# Lilypad_Schematic_1.net
KiCad netlist of a schematic drawn in Altium Designer
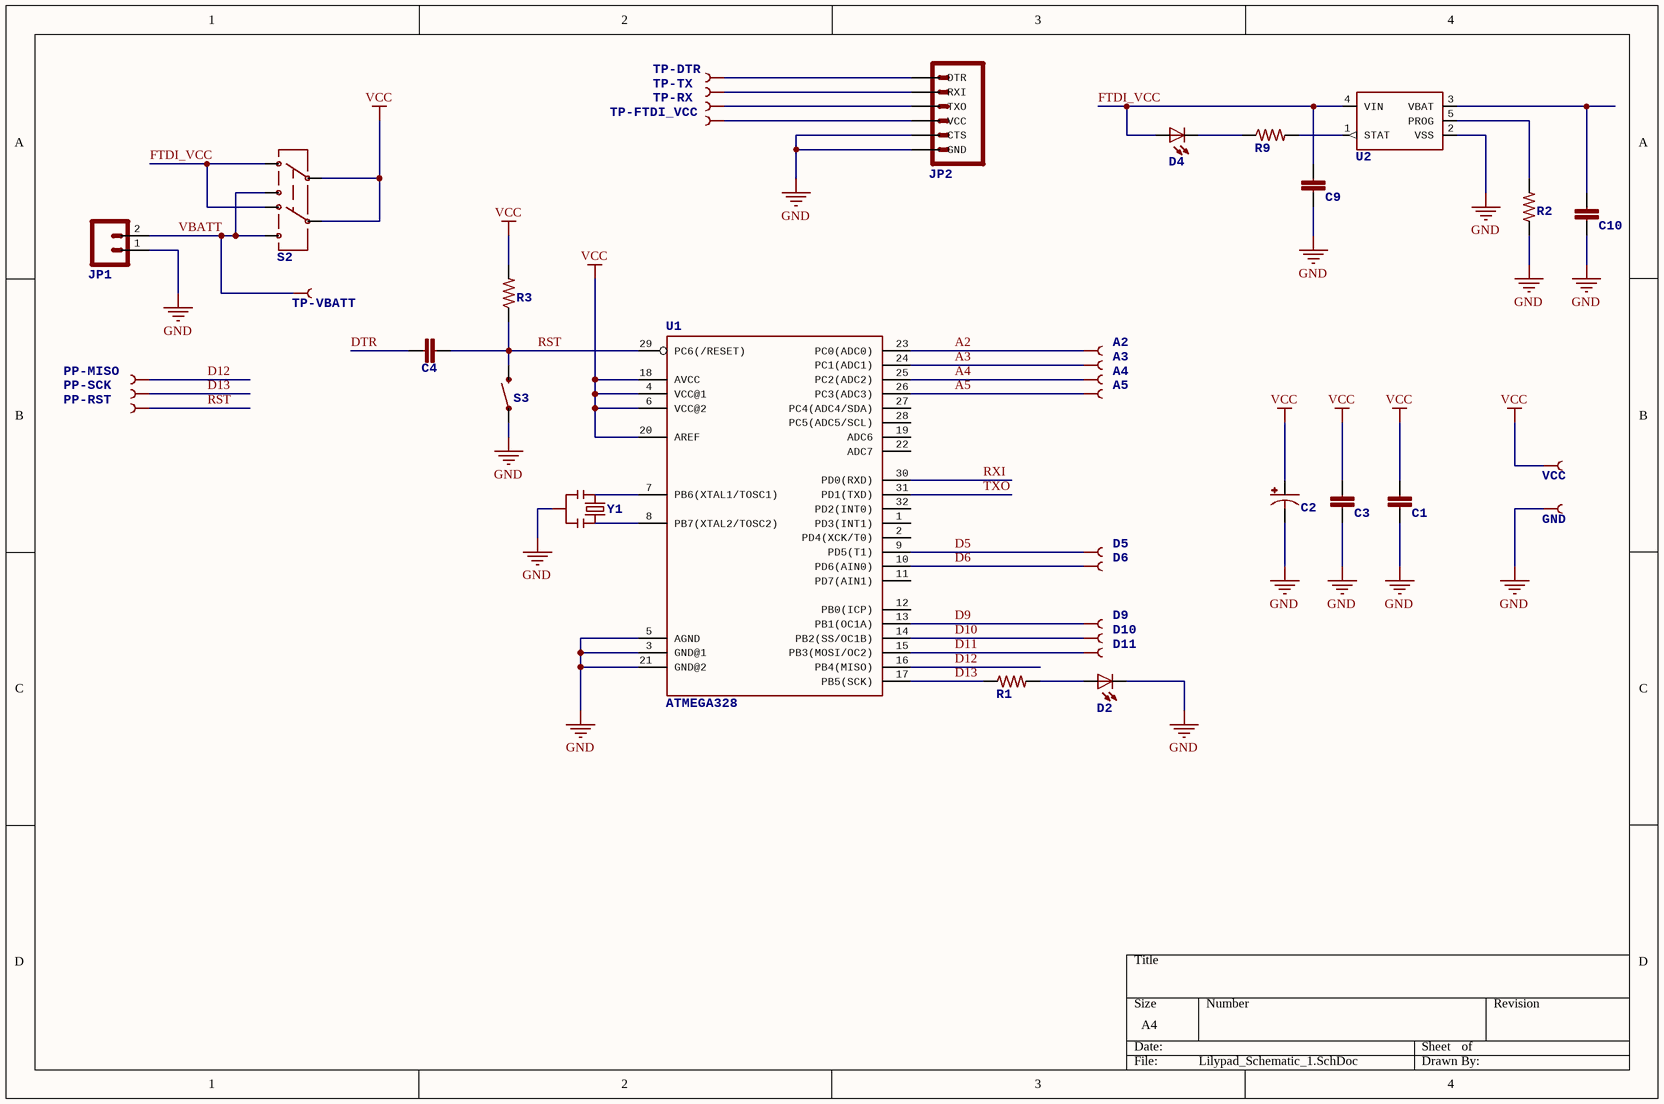
[diagram p0: Lilypad_Schematic_1.SchDoc]

(export (version "E")
  (design (tool "Eeschema 10.0.6"))
  (components
    (comp (ref "A2")
      (value "CONN")
      (footprint "PETAL-LONG-2")
      (libsource (lib "LilyPad Simple v2") (part "CONN"))
    )
    (comp (ref "A3")
      (value "CONN")
      (footprint "PETAL-LONG-2")
      (libsource (lib "LilyPad Simple v2") (part "CONN"))
    )
    (comp (ref "A4")
      (value "CONN")
      (footprint "PETAL-LONG-2")
      (libsource (lib "LilyPad Simple v2") (part "CONN"))
    )
    (comp (ref "A5")
      (value "CONN")
      (footprint "PETAL-LONG-2")
      (libsource (lib "LilyPad Simple v2") (part "CONN"))
    )
    (comp (ref "C1")
      (value "CAP0402-CAP")
      (footprint "0402-CAP")
      (libsource (lib "LilyPad Simple v2") (part "CAP0402-CAP"))
    )
    (comp (ref "C2")
      (value "CAP_POL3528")
      (footprint "EIA3528")
      (libsource (lib "LilyPad Simple v2") (part "CAP_POL3528"))
    )
    (comp (ref "C3")
      (value "CAP0402-CAP")
      (footprint "0402-CAP")
      (libsource (lib "LilyPad Simple v2") (part "CAP0402-CAP"))
    )
    (comp (ref "C4") (value "CAP0402-CAP") (footprint "0402-CAP") (libsource (lib "") (part "CAP0402-CAP_1")))
    (comp (ref "C9")
      (value "CAP0402-CAP")
      (footprint "0402-CAP")
      (libsource (lib "LilyPad Simple v2") (part "CAP0402-CAP"))
    )
    (comp (ref "C10")
      (value "CAP0402-CAP")
      (footprint "0402-CAP")
      (libsource (lib "LilyPad Simple v2") (part "CAP0402-CAP"))
    )
    (comp (ref "D2")
      (value "LED0603")
      (footprint "LED-0603")
      (libsource (lib "LilyPad Simple v2") (part "LED0603"))
    )
    (comp (ref "D4")
      (value "LED0603")
      (footprint "LED-0603")
      (libsource (lib "LilyPad Simple v2") (part "LED0603"))
    )
    (comp (ref "D5")
      (value "CONN")
      (footprint "PETAL-LONG-2")
      (libsource (lib "LilyPad Simple v2") (part "CONN"))
    )
    (comp (ref "D6")
      (value "CONN")
      (footprint "PETAL-LONG-2")
      (libsource (lib "LilyPad Simple v2") (part "CONN"))
    )
    (comp (ref "D9")
      (value "CONN")
      (footprint "PETAL-LONG-2")
      (libsource (lib "LilyPad Simple v2") (part "CONN"))
    )
    (comp (ref "D10")
      (value "CONN")
      (footprint "PETAL-LONG-2")
      (libsource (lib "LilyPad Simple v2") (part "CONN"))
    )
    (comp (ref "D11")
      (value "CONN")
      (footprint "PETAL-LONG-2")
      (libsource (lib "LilyPad Simple v2") (part "CONN"))
    )
    (comp (ref "GND")
      (value "CONN")
      (footprint "PETAL-LONG-2")
      (libsource (lib "LilyPad Simple v2") (part "CONN"))
    )
    (comp (ref "JP1")
      (value "M02-JST-2MM-SMT")
      (footprint "JST-2-SMD")
      (libsource (lib "LilyPad Simple v2") (part "M02-JST-2MM-SMT"))
    )
    (comp (ref "JP2")
      (value "ARDUINO_SERIAL_PROGRAMSMD")
      (footprint "1X06-SMD")
      (libsource (lib "LilyPad Simple v2") (part "ARDUINO_SERIAL_PROGRAMSMD"))
    )
    (comp (ref "PP-MISO")
      (value "TEST-POINT3X5")
      (footprint "PAD.03X.05")
      (libsource (lib "LilyPad Simple v2") (part "TEST-POINT3X5"))
    )
    (comp (ref "PP-RST")
      (value "TEST-POINT3X5")
      (footprint "PAD.03X.05")
      (libsource (lib "LilyPad Simple v2") (part "TEST-POINT3X5"))
    )
    (comp (ref "PP-SCK")
      (value "TEST-POINT3X5")
      (footprint "PAD.03X.05")
      (libsource (lib "LilyPad Simple v2") (part "TEST-POINT3X5"))
    )
    (comp (ref "R1")
      (value "RESISTOR0402-RES")
      (footprint "0402-RES")
      (libsource (lib "LilyPad Simple v2") (part "RESISTOR0402-RES"))
    )
    (comp (ref "R2")
      (value "RESISTOR0402-RES")
      (footprint "0402-RES")
      (libsource (lib "LilyPad Simple v2") (part "RESISTOR0402-RES"))
    )
    (comp (ref "R3")
      (value "RESISTOR0402-RES")
      (footprint "0402-RES")
      (libsource (lib "LilyPad Simple v2") (part "RESISTOR0402-RES"))
    )
    (comp (ref "R9")
      (value "RESISTOR0402-RES")
      (footprint "0402-RES")
      (libsource (lib "LilyPad Simple v2") (part "RESISTOR0402-RES"))
    )
    (comp (ref "S2")
      (value "AYZ0202")
      (footprint "AYZ0202")
      (libsource (lib "LilyPad Simple v2") (part "AYZ0202"))
    )
    (comp (ref "S3")
      (value "SWITCH-MOMENTARY-2SMD-2")
      (footprint "TACTILE_SWITCH_SMD-2")
      (libsource (lib "LilyPad Simple v2") (part "SWITCH-MOMENTARY-2SMD-2"))
    )
    (comp (ref "TP-DTR")
      (value "TEST-POINT3X5")
      (footprint "PAD.03X.05")
      (libsource (lib "LilyPad Simple v2") (part "TEST-POINT3X5"))
    )
    (comp (ref "TP-FTDI_VCC")
      (value "TEST-POINT3X5")
      (footprint "PAD.03X.05")
      (libsource (lib "LilyPad Simple v2") (part "TEST-POINT3X5"))
    )
    (comp (ref "TP-RX")
      (value "TEST-POINT3X5")
      (footprint "PAD.03X.05")
      (libsource (lib "LilyPad Simple v2") (part "TEST-POINT3X5"))
    )
    (comp (ref "TP-TX")
      (value "TEST-POINT3X5")
      (footprint "PAD.03X.05")
      (libsource (lib "LilyPad Simple v2") (part "TEST-POINT3X5"))
    )
    (comp (ref "TP-VBATT")
      (value "TEST-POINT3X5")
      (footprint "PAD.03X.05")
      (libsource (lib "LilyPad Simple v2") (part "TEST-POINT3X5"))
    )
    (comp (ref "U1")
      (value "ATMEGA328")
      (footprint "TQFP32-08")
      (libsource (lib "LilyPad Simple v2") (part "ATMEGA328"))
    )
    (comp (ref "U2")
      (value "MCP73831")
      (footprint "SOT23-5")
      (libsource (lib "LilyPad Simple v2") (part "MCP73831"))
    )
    (comp (ref "VCC")
      (value "CONN")
      (footprint "PETAL-LONG-2")
      (libsource (lib "LilyPad Simple v2") (part "CONN"))
    )
    (comp (ref "Y1")
      (value "RESONATORSMD")
      (footprint "RESONATOR-SMD")
      (libsource (lib "LilyPad Simple v2") (part "RESONATORSMD"))
    )
  )
  (nets
    (net (code "1") (name "/A2") (class "Default")
      (node (ref "A2") (pin "1") (pinfunction "1_1") (pintype "passive"))
      (node (ref "U1") (pin "23") (pinfunction "PC0(ADC0)_23") (pintype "passive"))
    )
    (net (code "2") (name "/A3") (class "Default")
      (node (ref "A3") (pin "1") (pinfunction "1_1") (pintype "passive"))
      (node (ref "U1") (pin "24") (pinfunction "PC1(ADC1)_24") (pintype "passive"))
    )
    (net (code "3") (name "/A4") (class "Default")
      (node (ref "A4") (pin "1") (pinfunction "1_1") (pintype "passive"))
      (node (ref "U1") (pin "25") (pinfunction "PC2(ADC2)_25") (pintype "passive"))
    )
    (net (code "4") (name "/A5") (class "Default")
      (node (ref "A5") (pin "1") (pinfunction "1_1") (pintype "passive"))
      (node (ref "U1") (pin "26") (pinfunction "PC3(ADC3)_26") (pintype "passive"))
    )
    (net (code "5") (name "/D5") (class "Default")
      (node (ref "D5") (pin "1") (pinfunction "1_1") (pintype "passive"))
      (node (ref "U1") (pin "9") (pinfunction "PD5(T1)_9") (pintype "passive"))
    )
    (net (code "6") (name "/D6") (class "Default")
      (node (ref "D6") (pin "1") (pinfunction "1_1") (pintype "passive"))
      (node (ref "U1") (pin "10") (pinfunction "PD6(AIN0)_10") (pintype "passive"))
    )
    (net (code "7") (name "/D9") (class "Default")
      (node (ref "D9") (pin "1") (pinfunction "1_1") (pintype "passive"))
      (node (ref "U1") (pin "13") (pinfunction "PB1(OC1A)_13") (pintype "passive"))
    )
    (net (code "8") (name "/D10") (class "Default")
      (node (ref "D10") (pin "1") (pinfunction "1_1") (pintype "passive"))
      (node (ref "U1") (pin "14") (pinfunction "PB2(SS/OC1B)_14") (pintype "passive"))
    )
    (net (code "9") (name "/D11") (class "Default")
      (node (ref "D11") (pin "1") (pinfunction "1_1") (pintype "passive"))
      (node (ref "U1") (pin "15") (pinfunction "PB3(MOSI/OC2)_15") (pintype "passive"))
    )
    (net (code "10") (name "/D12") (class "Default")
      (node (ref "PP-MISO") (pin "P$1") (pinfunction "1_P$1") (pintype "passive"))
      (node (ref "U1") (pin "16") (pinfunction "PB4(MISO)_16") (pintype "passive"))
    )
    (net (code "11") (name "/D13") (class "Default")
      (node (ref "PP-SCK") (pin "P$1") (pinfunction "1_P$1") (pintype "passive"))
      (node (ref "R1") (pin "1") (pinfunction "1_1") (pintype "passive"))
      (node (ref "U1") (pin "17") (pinfunction "PB5(SCK)_17") (pintype "passive"))
    )
    (net (code "12") (name "/DTR") (class "Default")
      (node (ref "C4") (pin "1") (pinfunction "1_1") (pintype "passive"))
    )
    (net (code "13") (name "/FTDI_VCC") (class "Default")
      (node (ref "C9") (pin "1") (pinfunction "1_1") (pintype "passive"))
      (node (ref "D4") (pin "A") (pinfunction "A_A") (pintype "passive"))
      (node (ref "S2") (pin "3") (pinfunction "1_3") (pintype "passive"))
      (node (ref "S2") (pin "6") (pinfunction "4_6") (pintype "passive"))
      (node (ref "U2") (pin "4") (pinfunction "VIN_4") (pintype "power_in"))
    )
    (net (code "14") (name "/RST") (class "Default")
      (node (ref "C4") (pin "2") (pinfunction "2_2") (pintype "passive"))
      (node (ref "PP-RST") (pin "P$1") (pinfunction "1_P$1") (pintype "passive"))
      (node (ref "R3") (pin "1") (pinfunction "1_1") (pintype "passive"))
      (node (ref "S3") (pin "1") (pinfunction "2_1") (pintype "passive"))
      (node (ref "U1") (pin "29") (pinfunction "PC6(/RESET)_29") (pintype "passive"))
    )
    (net (code "15") (name "/RXI") (class "Default")
      (node (ref "U1") (pin "30") (pinfunction "PD0(RXD)_30") (pintype "passive"))
    )
    (net (code "16") (name "/TXO") (class "Default")
      (node (ref "U1") (pin "31") (pinfunction "PD1(TXD)_31") (pintype "passive"))
    )
    (net (code "17") (name "/VBATT") (class "Default")
      (node (ref "JP1") (pin "2") (pinfunction "2_2") (pintype "passive"))
      (node (ref "S2") (pin "1") (pinfunction "3_1") (pintype "passive"))
      (node (ref "S2") (pin "4") (pinfunction "6_4") (pintype "passive"))
      (node (ref "TP-VBATT") (pin "P$1") (pinfunction "1_P$1") (pintype "passive"))
    )
    (net (code "18") (name "GND") (class "Default")
      (node (ref "C1") (pin "2") (pinfunction "2_2") (pintype "passive"))
      (node (ref "C10") (pin "2") (pinfunction "2_2") (pintype "passive"))
      (node (ref "C2") (pin "C") (pinfunction "-_C") (pintype "passive"))
      (node (ref "C3") (pin "2") (pinfunction "2_2") (pintype "passive"))
      (node (ref "C9") (pin "2") (pinfunction "2_2") (pintype "passive"))
      (node (ref "D2") (pin "C") (pinfunction "C_C") (pintype "passive"))
      (node (ref "GND") (pin "1") (pinfunction "1_1") (pintype "passive"))
      (node (ref "JP1") (pin "1") (pinfunction "1_1") (pintype "passive"))
      (node (ref "JP2") (pin "5") (pinfunction "CTS_5") (pintype "passive"))
      (node (ref "JP2") (pin "6") (pinfunction "GND_6") (pintype "passive"))
      (node (ref "R2") (pin "1") (pinfunction "1_1") (pintype "passive"))
      (node (ref "S3") (pin "2") (pinfunction "1_2") (pintype "passive"))
      (node (ref "U1") (pin "21") (pinfunction "GND@2_21") (pintype "passive"))
      (node (ref "U1") (pin "3") (pinfunction "GND@1_3") (pintype "passive"))
      (node (ref "U1") (pin "5") (pinfunction "AGND_5") (pintype "passive"))
      (node (ref "U2") (pin "2") (pinfunction "VSS_2") (pintype "power_in"))
      (node (ref "Y1") (pin "2") (pinfunction "2_2") (pintype "passive"))
    )
    (net (code "19") (name "Net-(D2-PadA)") (class "Default")
      (node (ref "D2") (pin "A") (pinfunction "A_A") (pintype "passive"))
      (node (ref "R1") (pin "2") (pinfunction "2_2") (pintype "passive"))
    )
    (net (code "20") (name "Net-(D4-PadC)") (class "Default")
      (node (ref "D4") (pin "C") (pinfunction "C_C") (pintype "passive"))
      (node (ref "R9") (pin "1") (pinfunction "1_1") (pintype "passive"))
    )
    (net (code "21") (name "Net-(JP2-DTR)") (class "Default")
      (node (ref "JP2") (pin "1") (pinfunction "DTR_1") (pintype "passive"))
      (node (ref "TP-DTR") (pin "P$1") (pinfunction "1_P$1") (pintype "passive"))
    )
    (net (code "22") (name "Net-(JP2-RXI)") (class "Default")
      (node (ref "JP2") (pin "2") (pinfunction "RXI_2") (pintype "passive"))
      (node (ref "TP-TX") (pin "P$1") (pinfunction "1_P$1") (pintype "passive"))
    )
    (net (code "23") (name "Net-(JP2-TXO)") (class "Default")
      (node (ref "JP2") (pin "3") (pinfunction "TXO_3") (pintype "passive"))
      (node (ref "TP-RX") (pin "P$1") (pinfunction "1_P$1") (pintype "passive"))
    )
    (net (code "24") (name "Net-(JP2-VCC)") (class "Default")
      (node (ref "JP2") (pin "4") (pinfunction "VCC_4") (pintype "passive"))
      (node (ref "TP-FTDI_VCC") (pin "P$1") (pinfunction "1_P$1") (pintype "passive"))
    )
    (net (code "25") (name "Net-(U1-PB6(XTAL1{slash}TOSC1))") (class "Default")
      (node (ref "U1") (pin "7") (pinfunction "PB6(XTAL1/TOSC1)_7") (pintype "passive"))
      (node (ref "Y1") (pin "1") (pinfunction "1_1") (pintype "passive"))
    )
    (net (code "26") (name "Net-(U1-PB7(XTAL2{slash}TOSC2))") (class "Default")
      (node (ref "U1") (pin "8") (pinfunction "PB7(XTAL2/TOSC2)_8") (pintype "passive"))
      (node (ref "Y1") (pin "3") (pinfunction "3_3") (pintype "passive"))
    )
    (net (code "27") (name "Net-(U2-PROG)") (class "Default")
      (node (ref "R2") (pin "2") (pinfunction "2_2") (pintype "passive"))
      (node (ref "U2") (pin "5") (pinfunction "PROG_5") (pintype "passive"))
    )
    (net (code "28") (name "Net-(U2-STAT)") (class "Default")
      (node (ref "R9") (pin "2") (pinfunction "2_2") (pintype "passive"))
      (node (ref "U2") (pin "1") (pinfunction "STAT_1") (pintype "output"))
    )
    (net (code "29") (name "Net-(U2-VBAT)") (class "Default")
      (node (ref "C10") (pin "1") (pinfunction "1_1") (pintype "passive"))
      (node (ref "U2") (pin "3") (pinfunction "VBAT_3") (pintype "power_in"))
    )
    (net (code "30") (name "VCC") (class "Default")
      (node (ref "C1") (pin "1") (pinfunction "1_1") (pintype "passive"))
      (node (ref "C2") (pin "A") (pinfunction "+_A") (pintype "passive"))
      (node (ref "C3") (pin "1") (pinfunction "1_1") (pintype "passive"))
      (node (ref "R3") (pin "2") (pinfunction "2_2") (pintype "passive"))
      (node (ref "S2") (pin "2") (pinfunction "2_2") (pintype "passive"))
      (node (ref "S2") (pin "5") (pinfunction "5_5") (pintype "passive"))
      (node (ref "U1") (pin "18") (pinfunction "AVCC_18") (pintype "passive"))
      (node (ref "U1") (pin "20") (pinfunction "AREF_20") (pintype "passive"))
      (node (ref "U1") (pin "4") (pinfunction "VCC@1_4") (pintype "passive"))
      (node (ref "U1") (pin "6") (pinfunction "VCC@2_6") (pintype "passive"))
      (node (ref "VCC") (pin "1") (pinfunction "1_1") (pintype "passive"))
    )
    (net (code "31") (name "unconnected-(U1-ADC6-Pad19)") (class "Default")
      (node (ref "U1") (pin "19") (pinfunction "ADC6_19") (pintype "passive"))
    )
    (net (code "32") (name "unconnected-(U1-ADC7-Pad22)") (class "Default")
      (node (ref "U1") (pin "22") (pinfunction "ADC7_22") (pintype "passive"))
    )
    (net (code "33") (name "unconnected-(U1-PB0(ICP)-Pad12)") (class "Default")
      (node (ref "U1") (pin "12") (pinfunction "PB0(ICP)_12") (pintype "passive"))
    )
    (net (code "34") (name "unconnected-(U1-PC4(ADC4{slash}SDA)-Pad27)") (class "Default")
      (node (ref "U1") (pin "27") (pinfunction "PC4(ADC4/SDA)_27") (pintype "passive"))
    )
    (net (code "35") (name "unconnected-(U1-PC5(ADC5{slash}SCL)-Pad28)") (class "Default")
      (node (ref "U1") (pin "28") (pinfunction "PC5(ADC5/SCL)_28") (pintype "passive"))
    )
    (net (code "36") (name "unconnected-(U1-PD2(INT0)-Pad32)") (class "Default")
      (node (ref "U1") (pin "32") (pinfunction "PD2(INT0)_32") (pintype "passive"))
    )
    (net (code "37") (name "unconnected-(U1-PD3(INT1)-Pad1)") (class "Default")
      (node (ref "U1") (pin "1") (pinfunction "PD3(INT1)_1") (pintype "passive"))
    )
    (net (code "38") (name "unconnected-(U1-PD4(XCK{slash}T0)-Pad2)") (class "Default")
      (node (ref "U1") (pin "2") (pinfunction "PD4(XCK/T0)_2") (pintype "passive"))
    )
    (net (code "39") (name "unconnected-(U1-PD7(AIN1)-Pad11)") (class "Default")
      (node (ref "U1") (pin "11") (pinfunction "PD7(AIN1)_11") (pintype "passive"))
    )
  )
)
